# speaker.net
KiCad netlist of a schematic drawn in Altium Designer
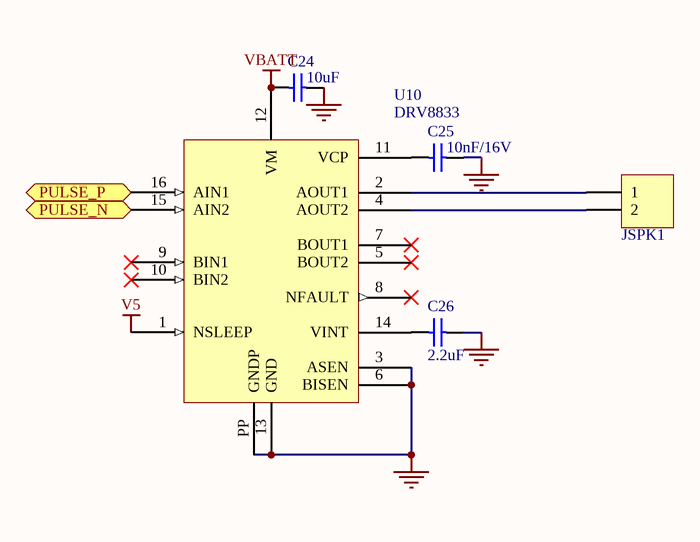
[diagram p0: speaker.SchDoc]

(export (version "E")
  (design (tool "Eeschema 10.0.6"))
  (components
    (comp (ref "C24")
      (value "10uF")
      (footprint "CAPC3216L")
      (description "Capacitor")
      (fields (field (name "PUBLISHER") "Altium Limited"))
      (libsource (lib "*") (part "Cap"))
    )
    (comp (ref "C25")
      (value "10nF/16V")
      (footprint "CAPC2012L")
      (description "Capacitor")
      (fields (field (name "PUBLISHER") "Altium Limited"))
      (libsource (lib "*") (part "Cap"))
    )
    (comp (ref "C26")
      (value "2.2uF")
      (footprint "CAPC2012L")
      (description "Capacitor")
      (fields (field (name "PUBLISHER") "Altium Limited"))
      (libsource (lib "*") (part "Cap"))
    )
    (comp (ref "JSPK1")
      (value "HDR1X2H")
      (footprint "HDR1X2H")
      (description "Header, 2-Pin")
      (fields (field (name "PUBLISHER") "Altium Limited"))
      (libsource (lib "*") (part "Header 2"))
    )
    (comp (ref "U10") (value "DRV8833") (footprint "DRV8833") (libsource (lib "components") (part "DRV8833")))
  )
  (nets
    (net (code "1") (name "/PULSE_N") (class "Default")
      (node (ref "U10") (pin "15") (pinfunction "AIN2_15") (pintype "input"))
    )
    (net (code "2") (name "/PULSE_P") (class "Default")
      (node (ref "U10") (pin "16") (pinfunction "AIN1_16") (pintype "input"))
    )
    (net (code "3") (name "GND") (class "Default")
      (node (ref "C24") (pin "1") (pinfunction "1_1") (pintype "passive"))
      (node (ref "C25") (pin "1") (pinfunction "1_1") (pintype "passive"))
      (node (ref "C26") (pin "1") (pinfunction "1_1") (pintype "passive"))
      (node (ref "U10") (pin "13") (pinfunction "GND_13") (pintype "power_in"))
      (node (ref "U10") (pin "3") (pinfunction "ASEN_3") (pintype "power_in"))
      (node (ref "U10") (pin "6") (pinfunction "BISEN_6") (pintype "power_in"))
      (node (ref "U10") (pin "PP") (pinfunction "GNDP_PP") (pintype "power_in"))
    )
    (net (code "4") (name "Net-(U10-AOUT1)") (class "Default")
      (node (ref "JSPK1") (pin "1") (pinfunction "1_1") (pintype "passive"))
      (node (ref "U10") (pin "2") (pinfunction "AOUT1_2") (pintype "power_in"))
    )
    (net (code "5") (name "Net-(U10-AOUT2)") (class "Default")
      (node (ref "JSPK1") (pin "2") (pinfunction "2_2") (pintype "passive"))
      (node (ref "U10") (pin "4") (pinfunction "AOUT2_4") (pintype "power_in"))
    )
    (net (code "6") (name "Net-(U10-VCP)") (class "Default")
      (node (ref "C25") (pin "2") (pinfunction "2_2") (pintype "passive"))
      (node (ref "U10") (pin "11") (pinfunction "VCP_11") (pintype "power_in"))
    )
    (net (code "7") (name "Net-(U10-VINT)") (class "Default")
      (node (ref "C26") (pin "2") (pinfunction "2_2") (pintype "passive"))
      (node (ref "U10") (pin "14") (pinfunction "VINT_14") (pintype "power_in"))
    )
    (net (code "8") (name "V5") (class "Default")
      (node (ref "U10") (pin "1") (pinfunction "NSLEEP_1") (pintype "input"))
    )
    (net (code "9") (name "VBATT") (class "Default")
      (node (ref "C24") (pin "2") (pinfunction "2_2") (pintype "passive"))
      (node (ref "U10") (pin "12") (pinfunction "VM_12") (pintype "power_in"))
    )
    (net (code "10") (name "unconnected-(U10-BIN1-Pad9)") (class "Default")
      (node (ref "U10") (pin "9") (pinfunction "BIN1_9") (pintype "input+no_connect"))
    )
    (net (code "11") (name "unconnected-(U10-BIN2-Pad10)") (class "Default")
      (node (ref "U10") (pin "10") (pinfunction "BIN2_10") (pintype "input+no_connect"))
    )
    (net (code "12") (name "unconnected-(U10-BOUT1-Pad7)") (class "Default")
      (node (ref "U10") (pin "7") (pinfunction "BOUT1_7") (pintype "power_in+no_connect"))
    )
    (net (code "13") (name "unconnected-(U10-BOUT2-Pad5)") (class "Default")
      (node (ref "U10") (pin "5") (pinfunction "BOUT2_5") (pintype "power_in+no_connect"))
    )
    (net (code "14") (name "unconnected-(U10-NFAULT-Pad8)") (class "Default")
      (node (ref "U10") (pin "8") (pinfunction "NFAULT_8") (pintype "output+no_connect"))
    )
  )
)
